# cape.net
KiCad netlist of a schematic drawn in EAGLE
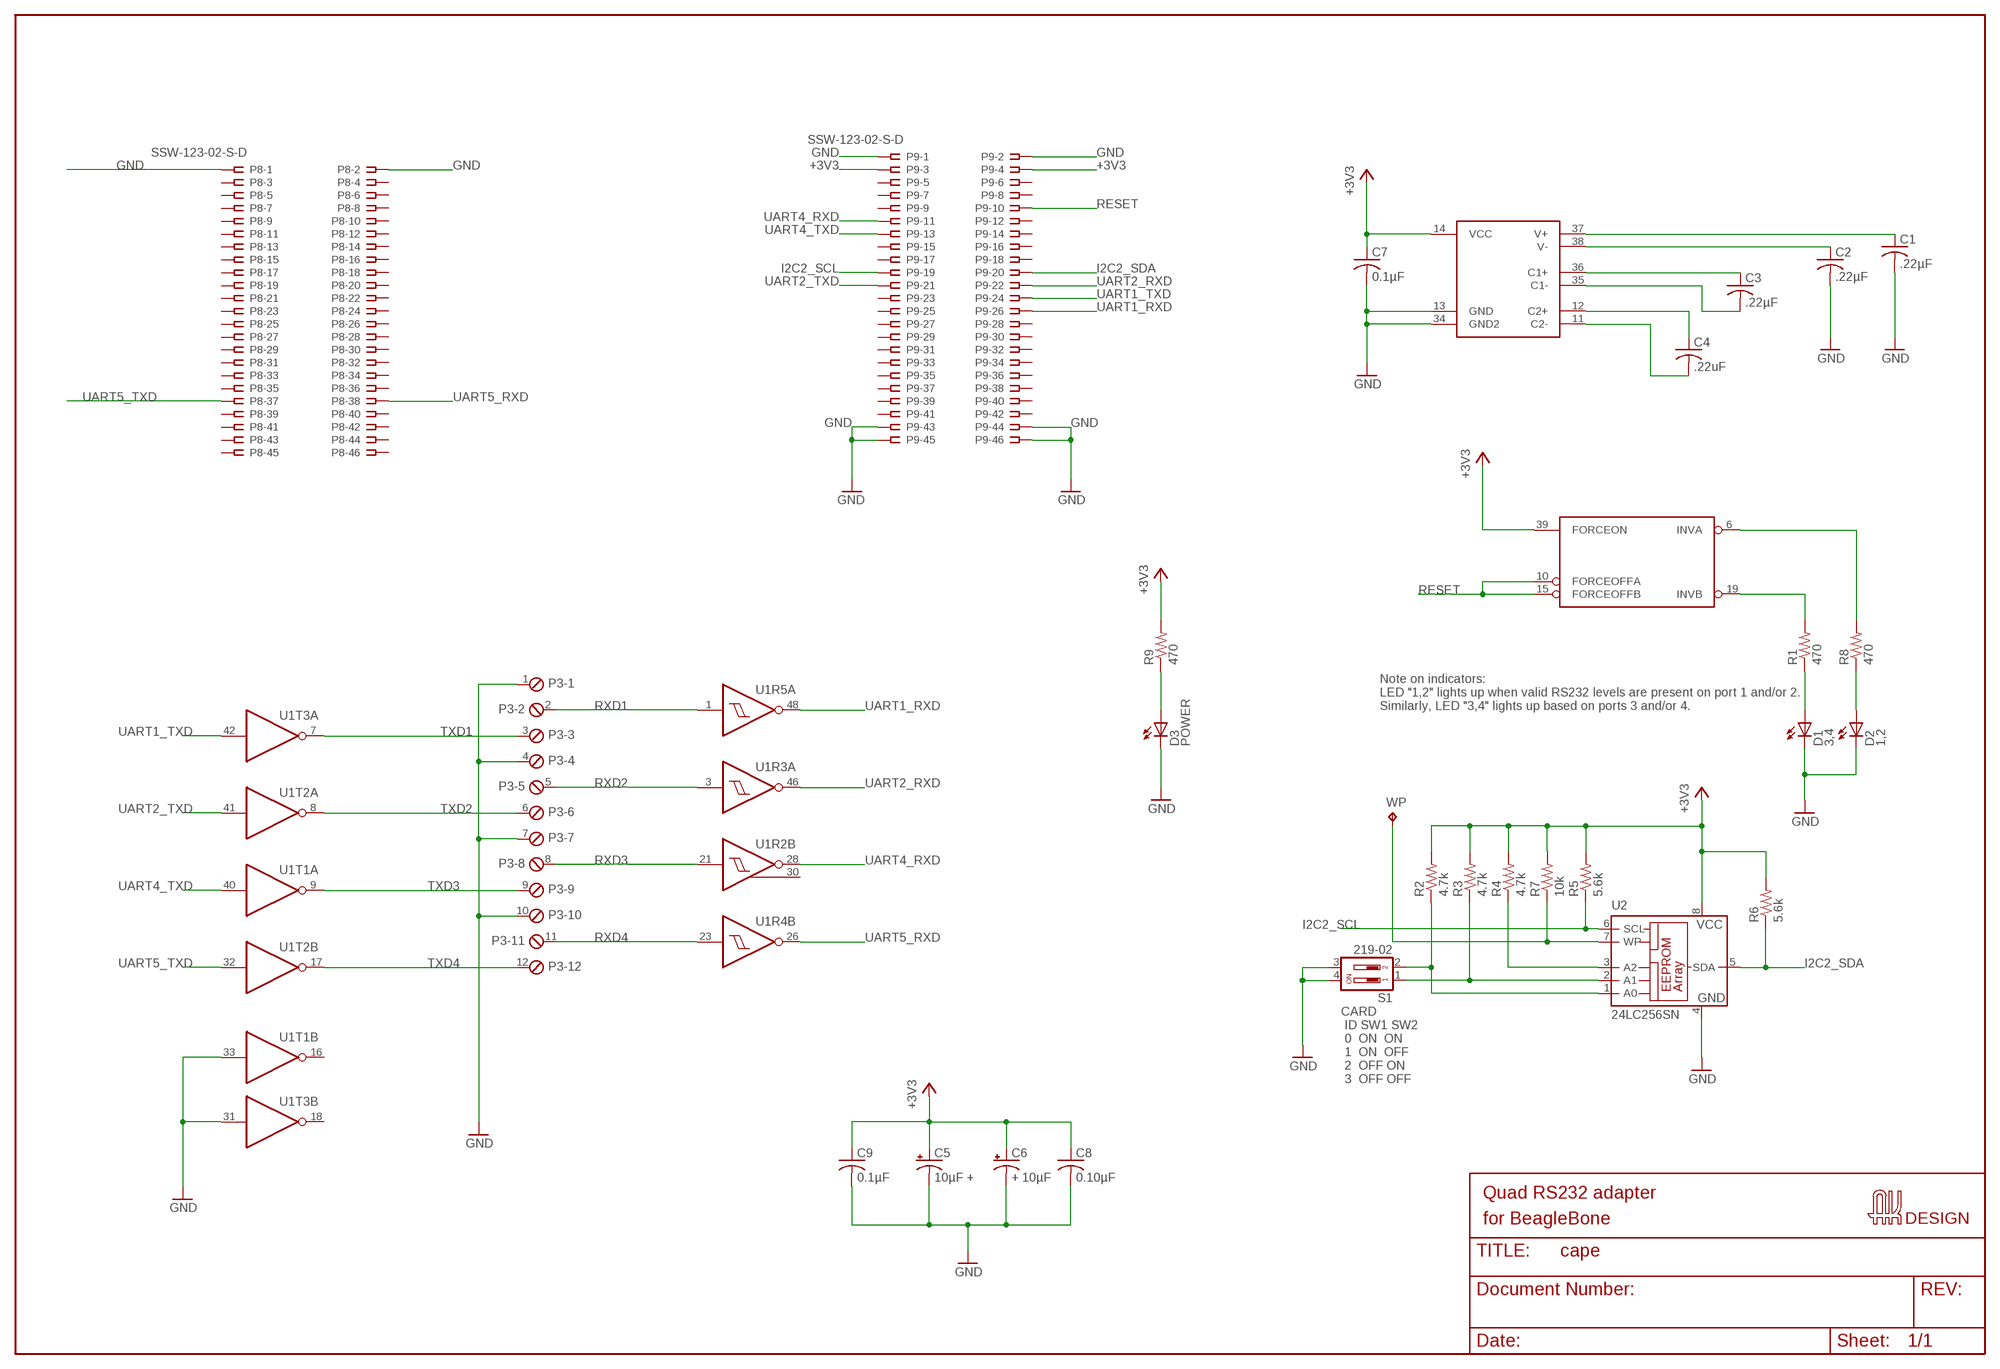
[diagram p0: schematic, sheet 1]

(export (version "E")
  (design (tool "Eeschema 10.0.6"))
  (components
    (comp (ref "C1")
      (value ".22µF")
      (footprint "eagle-import:C0603")
      (libsource (lib "eagle-import") (part "C-USC0603"))
    )
    (comp (ref "C2")
      (value ".22µF")
      (footprint "eagle-import:C0603")
      (libsource (lib "eagle-import") (part "C-USC0603"))
    )
    (comp (ref "C3")
      (value ".22µF")
      (footprint "eagle-import:C0603")
      (libsource (lib "eagle-import") (part "C-USC0603"))
    )
    (comp (ref "C4")
      (value ".22uF")
      (footprint "eagle-import:C0603")
      (libsource (lib "eagle-import") (part "C-USC0603"))
    )
    (comp (ref "C5")
      (value "10µF +")
      (footprint "eagle-import:C1206")
      (libsource (lib "eagle-import") (part "CPOL-USC1206"))
    )
    (comp (ref "C6")
      (value "+ 10µF")
      (footprint "eagle-import:C1206")
      (libsource (lib "eagle-import") (part "CPOL-USC1206"))
    )
    (comp (ref "C7")
      (value "0.1µF")
      (footprint "eagle-import:C0603")
      (libsource (lib "eagle-import") (part "C-USC0603"))
    )
    (comp (ref "C8")
      (value "0.10µF")
      (footprint "eagle-import:C0603")
      (libsource (lib "eagle-import") (part "C-USC0603"))
    )
    (comp (ref "C9")
      (value "0.1µF")
      (footprint "eagle-import:C0603")
      (libsource (lib "eagle-import") (part "C-USC0603"))
    )
    (comp (ref "D1")
      (value "3,4")
      (footprint "eagle-import:CHIPLED_0603")
      (libsource (lib "eagle-import") (part "LEDCHIPLED_0603"))
    )
    (comp (ref "D2")
      (value "1,2")
      (footprint "eagle-import:CHIPLED_0603")
      (libsource (lib "eagle-import") (part "LEDCHIPLED_0603"))
    )
    (comp (ref "D3")
      (value "POWER")
      (footprint "eagle-import:CHIPLED_0603")
      (libsource (lib "eagle-import") (part "LEDCHIPLED_0603"))
    )
    (comp (ref "P3")
      (value "MPT12")
      (footprint "eagle-import:12POL254")
      (libsource (lib "eagle-import") (part "MPT12"))
    )
    (comp (ref "P8")
      (value "SSW-123-02-S-D")
      (footprint "eagle-import:SSW-123-02-S-D")
      (libsource (lib "eagle-import") (part "SSW-123-02-S-D"))
    )
    (comp (ref "P9")
      (value "SSW-123-02-S-D")
      (footprint "eagle-import:SSW-123-02-S-D")
      (libsource (lib "eagle-import") (part "SSW-123-02-S-D"))
    )
    (comp (ref "R1")
      (value "470")
      (footprint "eagle-import:R0603")
      (libsource (lib "eagle-import") (part "R-US_R0603"))
    )
    (comp (ref "R2")
      (value "4.7k")
      (footprint "eagle-import:R0603")
      (libsource (lib "eagle-import") (part "R-US_R0603"))
    )
    (comp (ref "R3")
      (value "4.7k")
      (footprint "eagle-import:R0603")
      (libsource (lib "eagle-import") (part "R-US_R0603"))
    )
    (comp (ref "R4")
      (value "4.7k")
      (footprint "eagle-import:R0603")
      (libsource (lib "eagle-import") (part "R-US_R0603"))
    )
    (comp (ref "R5")
      (value "5.6k")
      (footprint "eagle-import:R0603")
      (libsource (lib "eagle-import") (part "R-US_R0603"))
    )
    (comp (ref "R6")
      (value "5.6k")
      (footprint "eagle-import:R0603")
      (libsource (lib "eagle-import") (part "R-US_R0603"))
    )
    (comp (ref "R7")
      (value "10k")
      (footprint "eagle-import:R0603")
      (libsource (lib "eagle-import") (part "R-US_R0603"))
    )
    (comp (ref "R8")
      (value "470")
      (footprint "eagle-import:R0603")
      (libsource (lib "eagle-import") (part "R-US_R0603"))
    )
    (comp (ref "R9")
      (value "470")
      (footprint "eagle-import:R0603")
      (libsource (lib "eagle-import") (part "R-US_R0603"))
    )
    (comp (ref "S1")
      (value "219-02")
      (footprint "eagle-import:CTS-219-02")
      (libsource (lib "eagle-import") (part "219-02"))
    )
    (comp (ref "U$3")
      (value "LOGO/PLACE")
      (footprint "eagle-import:LOGO_PLACE")
      (libsource (lib "eagle-import") (part "LOGO/PLACE"))
    )
    (comp (ref "U1")
      (value "SN75C23243")
      (footprint "eagle-import:SSOP48DL")
      (libsource (lib "eagle-import") (part "SN75C23243SN75C23243DL"))
    )
    (comp (ref "U2")
      (value "24LC256SN")
      (footprint "eagle-import:SO-08")
      (libsource (lib "eagle-import") (part "24SNLC256"))
    )
    (comp (ref "WP")
      (value "TPTP15SQ")
      (footprint "eagle-import:TP15SQ")
      (libsource (lib "eagle-import") (part "TPTP15SQ"))
    )
  )
  (nets
    (net (code "1") (name "+3V3") (class "Default")
      (node (ref "C5") (pin "1") (pinfunction "+_1") (pintype "passive"))
      (node (ref "C6") (pin "1") (pinfunction "+_1") (pintype "passive"))
      (node (ref "C7") (pin "1") (pinfunction "1_1") (pintype "passive"))
      (node (ref "C8") (pin "1") (pinfunction "1_1") (pintype "passive"))
      (node (ref "C9") (pin "1") (pinfunction "1_1") (pintype "passive"))
      (node (ref "P9") (pin "3") (pinfunction "1_3") (pintype "passive"))
      (node (ref "P9") (pin "4") (pinfunction "1_4") (pintype "passive"))
      (node (ref "R2") (pin "2") (pinfunction "2_2") (pintype "passive"))
      (node (ref "R3") (pin "2") (pinfunction "2_2") (pintype "passive"))
      (node (ref "R4") (pin "2") (pinfunction "2_2") (pintype "passive"))
      (node (ref "R5") (pin "2") (pinfunction "2_2") (pintype "passive"))
      (node (ref "R6") (pin "2") (pinfunction "2_2") (pintype "passive"))
      (node (ref "R7") (pin "2") (pinfunction "2_2") (pintype "passive"))
      (node (ref "R9") (pin "2") (pinfunction "2_2") (pintype "passive"))
      (node (ref "U1") (pin "14") (pinfunction "VCC_14") (pintype "power_in"))
      (node (ref "U1") (pin "39") (pinfunction "FORCEON_39") (pintype "input"))
      (node (ref "U2") (pin "8") (pinfunction "VCC_8") (pintype "power_in"))
    )
    (net (code "2") (name "/I2C2_SCL") (class "Default")
      (node (ref "P9") (pin "19") (pinfunction "1_19") (pintype "passive"))
      (node (ref "R5") (pin "1") (pinfunction "1_1") (pintype "passive"))
      (node (ref "U2") (pin "6") (pinfunction "SCL_6") (pintype "input"))
    )
    (net (code "3") (name "/I2C2_SDA") (class "Default")
      (node (ref "P9") (pin "20") (pinfunction "1_20") (pintype "passive"))
      (node (ref "R6") (pin "1") (pinfunction "1_1") (pintype "passive"))
      (node (ref "U2") (pin "5") (pinfunction "SDA_5") (pintype "bidirectional"))
    )
    (net (code "4") (name "/RESET") (class "Default")
      (node (ref "P9") (pin "10") (pinfunction "1_10") (pintype "passive"))
      (node (ref "U1") (pin "10") (pinfunction "FORCEOFFA_10") (pintype "input"))
      (node (ref "U1") (pin "15") (pinfunction "FORCEOFFB_15") (pintype "input"))
    )
    (net (code "5") (name "/RXD1") (class "Default")
      (node (ref "P3") (pin "2") (pinfunction "1_2") (pintype "passive"))
      (node (ref "U1") (pin "1") (pinfunction "I_1") (pintype "input"))
    )
    (net (code "6") (name "/RXD2") (class "Default")
      (node (ref "P3") (pin "5") (pinfunction "1_5") (pintype "passive"))
      (node (ref "U1") (pin "3") (pinfunction "I_3") (pintype "input"))
    )
    (net (code "7") (name "/RXD3") (class "Default")
      (node (ref "P3") (pin "8") (pinfunction "1_8") (pintype "passive"))
      (node (ref "U1") (pin "21") (pinfunction "I_21") (pintype "input"))
    )
    (net (code "8") (name "/RXD4") (class "Default")
      (node (ref "P3") (pin "11") (pinfunction "1_11") (pintype "passive"))
      (node (ref "U1") (pin "23") (pinfunction "I_23") (pintype "input"))
    )
    (net (code "9") (name "/TXD1") (class "Default")
      (node (ref "P3") (pin "3") (pinfunction "1_3") (pintype "passive"))
      (node (ref "U1") (pin "7") (pinfunction "O_7") (pintype "output"))
    )
    (net (code "10") (name "/TXD2") (class "Default")
      (node (ref "P3") (pin "6") (pinfunction "1_6") (pintype "passive"))
      (node (ref "U1") (pin "8") (pinfunction "O_8") (pintype "output"))
    )
    (net (code "11") (name "/TXD3") (class "Default")
      (node (ref "P3") (pin "9") (pinfunction "1_9") (pintype "passive"))
      (node (ref "U1") (pin "9") (pinfunction "O_9") (pintype "output"))
    )
    (net (code "12") (name "/TXD4") (class "Default")
      (node (ref "P3") (pin "12") (pinfunction "1_12") (pintype "passive"))
      (node (ref "U1") (pin "17") (pinfunction "O_17") (pintype "output"))
    )
    (net (code "13") (name "/UART1_RXD") (class "Default")
      (node (ref "P9") (pin "26") (pinfunction "1_26") (pintype "passive"))
      (node (ref "U1") (pin "48") (pinfunction "O_48") (pintype "output"))
    )
    (net (code "14") (name "/UART1_TXD") (class "Default")
      (node (ref "P9") (pin "24") (pinfunction "1_24") (pintype "passive"))
      (node (ref "U1") (pin "42") (pinfunction "I_42") (pintype "input"))
    )
    (net (code "15") (name "/UART2_RXD") (class "Default")
      (node (ref "P9") (pin "22") (pinfunction "1_22") (pintype "passive"))
      (node (ref "U1") (pin "46") (pinfunction "O_46") (pintype "output"))
    )
    (net (code "16") (name "/UART2_TXD") (class "Default")
      (node (ref "P9") (pin "21") (pinfunction "1_21") (pintype "passive"))
      (node (ref "U1") (pin "41") (pinfunction "I_41") (pintype "input"))
    )
    (net (code "17") (name "/UART4_RXD") (class "Default")
      (node (ref "P9") (pin "11") (pinfunction "1_11") (pintype "passive"))
      (node (ref "U1") (pin "28") (pinfunction "O_28") (pintype "output"))
    )
    (net (code "18") (name "/UART4_TXD") (class "Default")
      (node (ref "P9") (pin "13") (pinfunction "1_13") (pintype "passive"))
      (node (ref "U1") (pin "40") (pinfunction "I_40") (pintype "input"))
    )
    (net (code "19") (name "/UART5_RXD") (class "Default")
      (node (ref "P8") (pin "38") (pinfunction "1_38") (pintype "passive"))
      (node (ref "U1") (pin "26") (pinfunction "O_26") (pintype "output"))
    )
    (net (code "20") (name "/UART5_TXD") (class "Default")
      (node (ref "P8") (pin "37") (pinfunction "1_37") (pintype "passive"))
      (node (ref "U1") (pin "32") (pinfunction "I_32") (pintype "input"))
    )
    (net (code "21") (name "GND") (class "Default")
      (node (ref "C1") (pin "2") (pinfunction "2_2") (pintype "passive"))
      (node (ref "C2") (pin "2") (pinfunction "2_2") (pintype "passive"))
      (node (ref "C5") (pin "2") (pinfunction "-_2") (pintype "passive"))
      (node (ref "C6") (pin "2") (pinfunction "-_2") (pintype "passive"))
      (node (ref "C7") (pin "2") (pinfunction "2_2") (pintype "passive"))
      (node (ref "C8") (pin "2") (pinfunction "2_2") (pintype "passive"))
      (node (ref "C9") (pin "2") (pinfunction "2_2") (pintype "passive"))
      (node (ref "D1") (pin "C") (pinfunction "C_C") (pintype "passive"))
      (node (ref "D2") (pin "C") (pinfunction "C_C") (pintype "passive"))
      (node (ref "D3") (pin "C") (pinfunction "C_C") (pintype "passive"))
      (node (ref "P3") (pin "1") (pinfunction "1_1") (pintype "passive"))
      (node (ref "P3") (pin "10") (pinfunction "1_10") (pintype "passive"))
      (node (ref "P3") (pin "4") (pinfunction "1_4") (pintype "passive"))
      (node (ref "P3") (pin "7") (pinfunction "1_7") (pintype "passive"))
      (node (ref "P8") (pin "1") (pinfunction "1_1") (pintype "passive"))
      (node (ref "P8") (pin "2") (pinfunction "1_2") (pintype "passive"))
      (node (ref "P9") (pin "1") (pinfunction "1_1") (pintype "passive"))
      (node (ref "P9") (pin "2") (pinfunction "1_2") (pintype "passive"))
      (node (ref "P9") (pin "43") (pinfunction "1_43") (pintype "passive"))
      (node (ref "P9") (pin "44") (pinfunction "1_44") (pintype "passive"))
      (node (ref "P9") (pin "45") (pinfunction "1_45") (pintype "passive"))
      (node (ref "P9") (pin "46") (pinfunction "1_46") (pintype "passive"))
      (node (ref "S1") (pin "3") (pinfunction "3_3") (pintype "passive"))
      (node (ref "S1") (pin "4") (pinfunction "4_4") (pintype "passive"))
      (node (ref "U1") (pin "13") (pinfunction "GND_13") (pintype "power_in"))
      (node (ref "U1") (pin "31") (pinfunction "I_31") (pintype "input"))
      (node (ref "U1") (pin "33") (pinfunction "I_33") (pintype "input"))
      (node (ref "U1") (pin "34") (pinfunction "GND2_34") (pintype "power_in"))
      (node (ref "U2") (pin "4") (pinfunction "GND_4") (pintype "power_in"))
    )
    (net (code "22") (name "Net-(D1-PadA)") (class "Default")
      (node (ref "D1") (pin "A") (pinfunction "A_A") (pintype "passive"))
      (node (ref "R1") (pin "1") (pinfunction "1_1") (pintype "passive"))
    )
    (net (code "23") (name "Net-(D2-PadA)") (class "Default")
      (node (ref "D2") (pin "A") (pinfunction "A_A") (pintype "passive"))
      (node (ref "R8") (pin "1") (pinfunction "1_1") (pintype "passive"))
    )
    (net (code "24") (name "Net-(D3-PadA)") (class "Default")
      (node (ref "D3") (pin "A") (pinfunction "A_A") (pintype "passive"))
      (node (ref "R9") (pin "1") (pinfunction "1_1") (pintype "passive"))
    )
    (net (code "25") (name "Net-(U1A-INVA)") (class "Default")
      (node (ref "R8") (pin "2") (pinfunction "2_2") (pintype "passive"))
      (node (ref "U1") (pin "6") (pinfunction "INVA_6") (pintype "output"))
    )
    (net (code "26") (name "Net-(U1A-INVB)") (class "Default")
      (node (ref "R1") (pin "2") (pinfunction "2_2") (pintype "passive"))
      (node (ref "U1") (pin "19") (pinfunction "INVB_19") (pintype "output"))
    )
    (net (code "27") (name "Net-(U1B-C1+)") (class "Default")
      (node (ref "C3") (pin "1") (pinfunction "1_1") (pintype "passive"))
      (node (ref "U1") (pin "36") (pinfunction "C1+_36") (pintype "power_in"))
    )
    (net (code "28") (name "Net-(U1B-C1-)") (class "Default")
      (node (ref "C3") (pin "2") (pinfunction "2_2") (pintype "passive"))
      (node (ref "U1") (pin "35") (pinfunction "C1-_35") (pintype "power_in"))
    )
    (net (code "29") (name "Net-(U1B-C2+)") (class "Default")
      (node (ref "C4") (pin "1") (pinfunction "1_1") (pintype "passive"))
      (node (ref "U1") (pin "12") (pinfunction "C2+_12") (pintype "power_in"))
    )
    (net (code "30") (name "Net-(U1B-C2-)") (class "Default")
      (node (ref "C4") (pin "2") (pinfunction "2_2") (pintype "passive"))
      (node (ref "U1") (pin "11") (pinfunction "C2-_11") (pintype "power_in"))
    )
    (net (code "31") (name "Net-(U1B-V+)") (class "Default")
      (node (ref "C1") (pin "1") (pinfunction "1_1") (pintype "passive"))
      (node (ref "U1") (pin "37") (pinfunction "V+_37") (pintype "power_in"))
    )
    (net (code "32") (name "Net-(U1B-V-)") (class "Default")
      (node (ref "C2") (pin "1") (pinfunction "1_1") (pintype "passive"))
      (node (ref "U1") (pin "38") (pinfunction "V-_38") (pintype "power_in"))
    )
    (net (code "33") (name "Net-(U2-A0)") (class "Default")
      (node (ref "R2") (pin "1") (pinfunction "1_1") (pintype "passive"))
      (node (ref "S1") (pin "2") (pinfunction "2_2") (pintype "passive"))
      (node (ref "U2") (pin "1") (pinfunction "A0_1") (pintype "input"))
    )
    (net (code "34") (name "Net-(U2-A1)") (class "Default")
      (node (ref "R3") (pin "1") (pinfunction "1_1") (pintype "passive"))
      (node (ref "S1") (pin "1") (pinfunction "1_1") (pintype "passive"))
      (node (ref "U2") (pin "2") (pinfunction "A1_2") (pintype "input"))
    )
    (net (code "35") (name "Net-(U2-A2)") (class "Default")
      (node (ref "R4") (pin "1") (pinfunction "1_1") (pintype "passive"))
      (node (ref "U2") (pin "3") (pinfunction "A2_3") (pintype "input"))
    )
    (net (code "36") (name "Net-(U2-WP)") (class "Default")
      (node (ref "R7") (pin "1") (pinfunction "1_1") (pintype "passive"))
      (node (ref "U2") (pin "7") (pinfunction "WP_7") (pintype "input"))
      (node (ref "WP") (pin "TP") (pinfunction "TP_TP") (pintype "input"))
    )
    (net (code "37") (name "unconnected-(P8AA-1-Pad33)") (class "Default")
      (node (ref "P8") (pin "33") (pinfunction "1_33") (pintype "passive"))
    )
    (net (code "38") (name "unconnected-(P8AB-1-Pad34)") (class "Default")
      (node (ref "P8") (pin "34") (pinfunction "1_34") (pintype "passive"))
    )
    (net (code "39") (name "unconnected-(P8AC-1-Pad35)") (class "Default")
      (node (ref "P8") (pin "35") (pinfunction "1_35") (pintype "passive"))
    )
    (net (code "40") (name "unconnected-(P8AD-1-Pad36)") (class "Default")
      (node (ref "P8") (pin "36") (pinfunction "1_36") (pintype "passive"))
    )
    (net (code "41") (name "unconnected-(P8AG-1-Pad39)") (class "Default")
      (node (ref "P8") (pin "39") (pinfunction "1_39") (pintype "passive"))
    )
    (net (code "42") (name "unconnected-(P8AH-1-Pad4)") (class "Default")
      (node (ref "P8") (pin "4") (pinfunction "1_4") (pintype "passive"))
    )
    (net (code "43") (name "unconnected-(P8AI-1-Pad40)") (class "Default")
      (node (ref "P8") (pin "40") (pinfunction "1_40") (pintype "passive"))
    )
    (net (code "44") (name "unconnected-(P8AJ-1-Pad41)") (class "Default")
      (node (ref "P8") (pin "41") (pinfunction "1_41") (pintype "passive"))
    )
    (net (code "45") (name "unconnected-(P8AK-1-Pad42)") (class "Default")
      (node (ref "P8") (pin "42") (pinfunction "1_42") (pintype "passive"))
    )
    (net (code "46") (name "unconnected-(P8AL-1-Pad43)") (class "Default")
      (node (ref "P8") (pin "43") (pinfunction "1_43") (pintype "passive"))
    )
    (net (code "47") (name "unconnected-(P8AM-1-Pad44)") (class "Default")
      (node (ref "P8") (pin "44") (pinfunction "1_44") (pintype "passive"))
    )
    (net (code "48") (name "unconnected-(P8AN-1-Pad45)") (class "Default")
      (node (ref "P8") (pin "45") (pinfunction "1_45") (pintype "passive"))
    )
    (net (code "49") (name "unconnected-(P8AO-1-Pad46)") (class "Default")
      (node (ref "P8") (pin "46") (pinfunction "1_46") (pintype "passive"))
    )
    (net (code "50") (name "unconnected-(P8AP-1-Pad5)") (class "Default")
      (node (ref "P8") (pin "5") (pinfunction "1_5") (pintype "passive"))
    )
    (net (code "51") (name "unconnected-(P8AQ-1-Pad6)") (class "Default")
      (node (ref "P8") (pin "6") (pinfunction "1_6") (pintype "passive"))
    )
    (net (code "52") (name "unconnected-(P8AR-1-Pad7)") (class "Default")
      (node (ref "P8") (pin "7") (pinfunction "1_7") (pintype "passive"))
    )
    (net (code "53") (name "unconnected-(P8AS-1-Pad8)") (class "Default")
      (node (ref "P8") (pin "8") (pinfunction "1_8") (pintype "passive"))
    )
    (net (code "54") (name "unconnected-(P8AT-1-Pad9)") (class "Default")
      (node (ref "P8") (pin "9") (pinfunction "1_9") (pintype "passive"))
    )
    (net (code "55") (name "unconnected-(P8B-1-Pad10)") (class "Default")
      (node (ref "P8") (pin "10") (pinfunction "1_10") (pintype "passive"))
    )
    (net (code "56") (name "unconnected-(P8C-1-Pad11)") (class "Default")
      (node (ref "P8") (pin "11") (pinfunction "1_11") (pintype "passive"))
    )
    (net (code "57") (name "unconnected-(P8D-1-Pad12)") (class "Default")
      (node (ref "P8") (pin "12") (pinfunction "1_12") (pintype "passive"))
    )
    (net (code "58") (name "unconnected-(P8E-1-Pad13)") (class "Default")
      (node (ref "P8") (pin "13") (pinfunction "1_13") (pintype "passive"))
    )
    (net (code "59") (name "unconnected-(P8F-1-Pad14)") (class "Default")
      (node (ref "P8") (pin "14") (pinfunction "1_14") (pintype "passive"))
    )
    (net (code "60") (name "unconnected-(P8G-1-Pad15)") (class "Default")
      (node (ref "P8") (pin "15") (pinfunction "1_15") (pintype "passive"))
    )
    (net (code "61") (name "unconnected-(P8H-1-Pad16)") (class "Default")
      (node (ref "P8") (pin "16") (pinfunction "1_16") (pintype "passive"))
    )
    (net (code "62") (name "unconnected-(P8I-1-Pad17)") (class "Default")
      (node (ref "P8") (pin "17") (pinfunction "1_17") (pintype "passive"))
    )
    (net (code "63") (name "unconnected-(P8J-1-Pad18)") (class "Default")
      (node (ref "P8") (pin "18") (pinfunction "1_18") (pintype "passive"))
    )
    (net (code "64") (name "unconnected-(P8K-1-Pad19)") (class "Default")
      (node (ref "P8") (pin "19") (pinfunction "1_19") (pintype "passive"))
    )
    (net (code "65") (name "unconnected-(P8M-1-Pad20)") (class "Default")
      (node (ref "P8") (pin "20") (pinfunction "1_20") (pintype "passive"))
    )
    (net (code "66") (name "unconnected-(P8N-1-Pad21)") (class "Default")
      (node (ref "P8") (pin "21") (pinfunction "1_21") (pintype "passive"))
    )
    (net (code "67") (name "unconnected-(P8O-1-Pad22)") (class "Default")
      (node (ref "P8") (pin "22") (pinfunction "1_22") (pintype "passive"))
    )
    (net (code "68") (name "unconnected-(P8P-1-Pad23)") (class "Default")
      (node (ref "P8") (pin "23") (pinfunction "1_23") (pintype "passive"))
    )
    (net (code "69") (name "unconnected-(P8Q-1-Pad24)") (class "Default")
      (node (ref "P8") (pin "24") (pinfunction "1_24") (pintype "passive"))
    )
    (net (code "70") (name "unconnected-(P8R-1-Pad25)") (class "Default")
      (node (ref "P8") (pin "25") (pinfunction "1_25") (pintype "passive"))
    )
    (net (code "71") (name "unconnected-(P8S-1-Pad26)") (class "Default")
      (node (ref "P8") (pin "26") (pinfunction "1_26") (pintype "passive"))
    )
    (net (code "72") (name "unconnected-(P8T-1-Pad27)") (class "Default")
      (node (ref "P8") (pin "27") (pinfunction "1_27") (pintype "passive"))
    )
    (net (code "73") (name "unconnected-(P8U-1-Pad28)") (class "Default")
      (node (ref "P8") (pin "28") (pinfunction "1_28") (pintype "passive"))
    )
    (net (code "74") (name "unconnected-(P8V-1-Pad29)") (class "Default")
      (node (ref "P8") (pin "29") (pinfunction "1_29") (pintype "passive"))
    )
    (net (code "75") (name "unconnected-(P8W-1-Pad3)") (class "Default")
      (node (ref "P8") (pin "3") (pinfunction "1_3") (pintype "passive"))
    )
    (net (code "76") (name "unconnected-(P8X-1-Pad30)") (class "Default")
      (node (ref "P8") (pin "30") (pinfunction "1_30") (pintype "passive"))
    )
    (net (code "77") (name "unconnected-(P8Y-1-Pad31)") (class "Default")
      (node (ref "P8") (pin "31") (pinfunction "1_31") (pintype "passive"))
    )
    (net (code "78") (name "unconnected-(P8Z-1-Pad32)") (class "Default")
      (node (ref "P8") (pin "32") (pinfunction "1_32") (pintype "passive"))
    )
    (net (code "79") (name "unconnected-(P9AA-1-Pad33)") (class "Default")
      (node (ref "P9") (pin "33") (pinfunction "1_33") (pintype "passive"))
    )
    (net (code "80") (name "unconnected-(P9AB-1-Pad34)") (class "Default")
      (node (ref "P9") (pin "34") (pinfunction "1_34") (pintype "passive"))
    )
    (net (code "81") (name "unconnected-(P9AC-1-Pad35)") (class "Default")
      (node (ref "P9") (pin "35") (pinfunction "1_35") (pintype "passive"))
    )
    (net (code "82") (name "unconnected-(P9AD-1-Pad36)") (class "Default")
      (node (ref "P9") (pin "36") (pinfunction "1_36") (pintype "passive"))
    )
    (net (code "83") (name "unconnected-(P9AE-1-Pad37)") (class "Default")
      (node (ref "P9") (pin "37") (pinfunction "1_37") (pintype "passive"))
    )
    (net (code "84") (name "unconnected-(P9AF-1-Pad38)") (class "Default")
      (node (ref "P9") (pin "38") (pinfunction "1_38") (pintype "passive"))
    )
    (net (code "85") (name "unconnected-(P9AG-1-Pad39)") (class "Default")
      (node (ref "P9") (pin "39") (pinfunction "1_39") (pintype "passive"))
    )
    (net (code "86") (name "unconnected-(P9AI-1-Pad40)") (class "Default")
      (node (ref "P9") (pin "40") (pinfunction "1_40") (pintype "passive"))
    )
    (net (code "87") (name "unconnected-(P9AJ-1-Pad41)") (class "Default")
      (node (ref "P9") (pin "41") (pinfunction "1_41") (pintype "passive"))
    )
    (net (code "88") (name "unconnected-(P9AK-1-Pad42)") (class "Default")
      (node (ref "P9") (pin "42") (pinfunction "1_42") (pintype "passive"))
    )
    (net (code "89") (name "unconnected-(P9AP-1-Pad5)") (class "Default")
      (node (ref "P9") (pin "5") (pinfunction "1_5") (pintype "passive"))
    )
    (net (code "90") (name "unconnected-(P9AQ-1-Pad6)") (class "Default")
      (node (ref "P9") (pin "6") (pinfunction "1_6") (pintype "passive"))
    )
    (net (code "91") (name "unconnected-(P9AR-1-Pad7)") (class "Default")
      (node (ref "P9") (pin "7") (pinfunction "1_7") (pintype "passive"))
    )
    (net (code "92") (name "unconnected-(P9AS-1-Pad8)") (class "Default")
      (node (ref "P9") (pin "8") (pinfunction "1_8") (pintype "passive"))
    )
    (net (code "93") (name "unconnected-(P9AT-1-Pad9)") (class "Default")
      (node (ref "P9") (pin "9") (pinfunction "1_9") (pintype "passive"))
    )
    (net (code "94") (name "unconnected-(P9D-1-Pad12)") (class "Default")
      (node (ref "P9") (pin "12") (pinfunction "1_12") (pintype "passive"))
    )
    (net (code "95") (name "unconnected-(P9F-1-Pad14)") (class "Default")
      (node (ref "P9") (pin "14") (pinfunction "1_14") (pintype "passive"))
    )
    (net (code "96") (name "unconnected-(P9G-1-Pad15)") (class "Default")
      (node (ref "P9") (pin "15") (pinfunction "1_15") (pintype "passive"))
    )
    (net (code "97") (name "unconnected-(P9H-1-Pad16)") (class "Default")
      (node (ref "P9") (pin "16") (pinfunction "1_16") (pintype "passive"))
    )
    (net (code "98") (name "unconnected-(P9I-1-Pad17)") (class "Default")
      (node (ref "P9") (pin "17") (pinfunction "1_17") (pintype "passive"))
    )
    (net (code "99") (name "unconnected-(P9J-1-Pad18)") (class "Default")
      (node (ref "P9") (pin "18") (pinfunction "1_18") (pintype "passive"))
    )
    (net (code "100") (name "unconnected-(P9P-1-Pad23)") (class "Default")
      (node (ref "P9") (pin "23") (pinfunction "1_23") (pintype "passive"))
    )
    (net (code "101") (name "unconnected-(P9R-1-Pad25)") (class "Default")
      (node (ref "P9") (pin "25") (pinfunction "1_25") (pintype "passive"))
    )
    (net (code "102") (name "unconnected-(P9T-1-Pad27)") (class "Default")
      (node (ref "P9") (pin "27") (pinfunction "1_27") (pintype "passive"))
    )
    (net (code "103") (name "unconnected-(P9U-1-Pad28)") (class "Default")
      (node (ref "P9") (pin "28") (pinfunction "1_28") (pintype "passive"))
    )
    (net (code "104") (name "unconnected-(P9V-1-Pad29)") (class "Default")
      (node (ref "P9") (pin "29") (pinfunction "1_29") (pintype "passive"))
    )
    (net (code "105") (name "unconnected-(P9X-1-Pad30)") (class "Default")
      (node (ref "P9") (pin "30") (pinfunction "1_30") (pintype "passive"))
    )
    (net (code "106") (name "unconnected-(P9Y-1-Pad31)") (class "Default")
      (node (ref "P9") (pin "31") (pinfunction "1_31") (pintype "passive"))
    )
    (net (code "107") (name "unconnected-(P9Z-1-Pad32)") (class "Default")
      (node (ref "P9") (pin "32") (pinfunction "1_32") (pintype "passive"))
    )
    (net (code "108") (name "unconnected-(U1F-OINV-Pad30)") (class "Default")
      (node (ref "U1") (pin "30") (pinfunction "OINV_30") (pintype "output"))
    )
    (net (code "109") (name "unconnected-(U1N-O-Pad16)") (class "Default")
      (node (ref "U1") (pin "16") (pinfunction "O_16") (pintype "output"))
    )
    (net (code "110") (name "unconnected-(U1R-O-Pad18)") (class "Default")
      (node (ref "U1") (pin "18") (pinfunction "O_18") (pintype "output"))
    )
  )
)
